# Input_Connector.net
KiCad netlist of a schematic drawn in Altium Designer
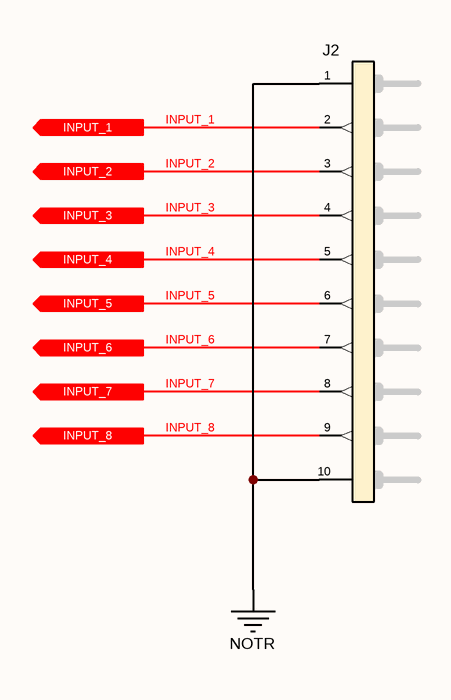
[diagram p0: Input Connector.SchDoc]

(export (version "E")
  (design (tool "Eeschema 10.0.6"))
  (components
    (comp (ref "J2")
      (value "2.54 mm Pitch 8P Male Connector")
      (footprint "Pin Header 1x10 TH Pitch 2.54mm")
      (description "Headers & Wire Housings BREAKAWAY HDR VERT 8")
      (fields (field (name "MANUFACTURER PART NUMBER") "22-28-4103"))
      (libsource (lib "Akkoyun") (part "Connector - Male Header 10P (2.54)"))
    )
  )
  (nets
    (net (code "1") (name "/INPUT_1") (class "Default")
      (node (ref "J2") (pin "2") (pinfunction "Pin-2_2") (pintype "output"))
    )
    (net (code "2") (name "/INPUT_2") (class "Default")
      (node (ref "J2") (pin "3") (pinfunction "Pin-3_3") (pintype "output"))
    )
    (net (code "3") (name "/INPUT_3") (class "Default")
      (node (ref "J2") (pin "4") (pinfunction "Pin-4_4") (pintype "output"))
    )
    (net (code "4") (name "/INPUT_4") (class "Default")
      (node (ref "J2") (pin "5") (pinfunction "Pin-5_5") (pintype "output"))
    )
    (net (code "5") (name "/INPUT_5") (class "Default")
      (node (ref "J2") (pin "6") (pinfunction "Pin-6_6") (pintype "output"))
    )
    (net (code "6") (name "/INPUT_6") (class "Default")
      (node (ref "J2") (pin "7") (pinfunction "Pin-7_7") (pintype "output"))
    )
    (net (code "7") (name "/INPUT_7") (class "Default")
      (node (ref "J2") (pin "8") (pinfunction "Pin-8_8") (pintype "output"))
    )
    (net (code "8") (name "/INPUT_8") (class "Default")
      (node (ref "J2") (pin "9") (pinfunction "Pin-9_9") (pintype "output"))
    )
    (net (code "9") (name "NOTR") (class "Default")
      (node (ref "J2") (pin "1") (pinfunction "Pin-1_1") (pintype "passive"))
      (node (ref "J2") (pin "10") (pinfunction "Pin-10_10") (pintype "passive"))
    )
  )
)
